# Connectors___Switch_Buttons.net
KiCad netlist of a schematic drawn in Altium Designer
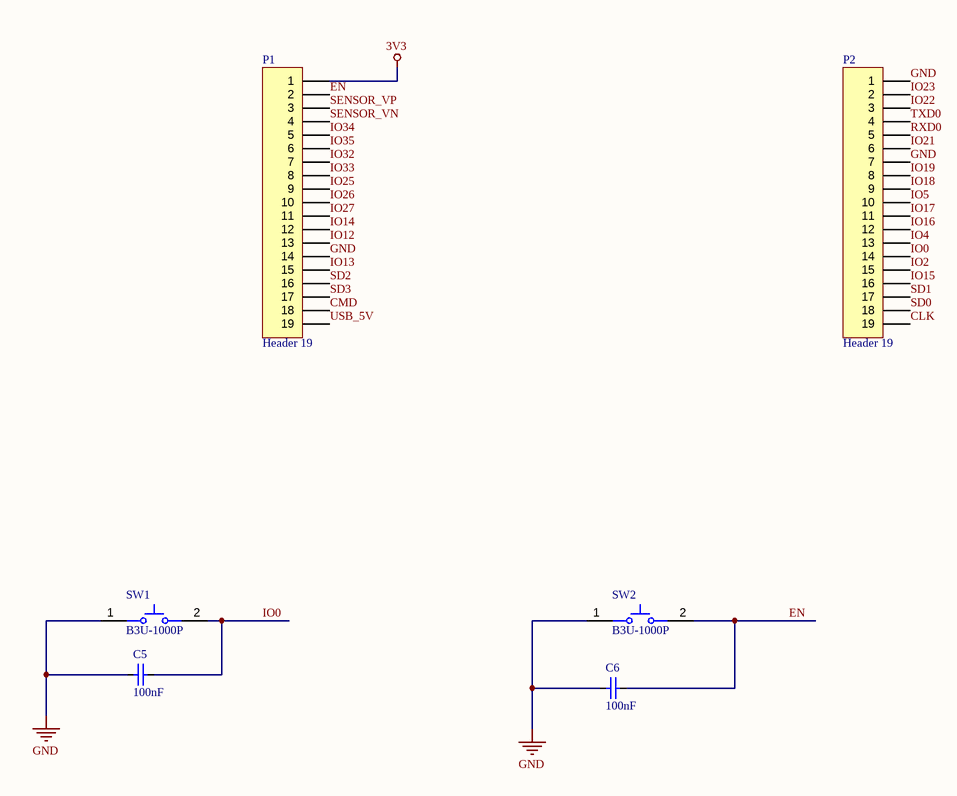
[diagram p0: Connectors_&_Switch_Buttons.SchDoc]

(export (version "E")
  (design (tool "Eeschema 10.0.6"))
  (components
    (comp (ref "C5")
      (value "100nF")
      (footprint "0603C_L")
      (fields
        (field (name "MANUFACTURER") "Yageo")
        (field (name "MANUFACTURER PART NUMBER") "CC0603ZRY5V9BB104")
        (field (name "Comment") "Cap100nF_50V_0603")
        (field (name "SOURCE") "WCT.SCHLIB")
      )
      (libsource (lib "Kylian Siemou Diemou Tchoya") (part "Cap100nF_50V_0603"))
    )
    (comp (ref "C6")
      (value "100nF")
      (footprint "0603C_L")
      (fields
        (field (name "MANUFACTURER") "Yageo")
        (field (name "MANUFACTURER PART NUMBER") "CC0603ZRY5V9BB104")
        (field (name "Comment") "Cap100nF_50V_0603")
        (field (name "SOURCE") "WCT.SCHLIB")
      )
      (libsource (lib "Kylian Siemou Diemou Tchoya") (part "Cap100nF_50V_0603"))
    )
    (comp (ref "P1")
      (value "Header 19")
      (footprint "HDR1X19")
      (description "Header, 19-Pin")
      (fields (field (name "PUBLISHER") "Altium Limited"))
      (libsource (lib "Miscellaneous Connectors") (part "Header 19"))
    )
    (comp (ref "P2")
      (value "Header 19")
      (footprint "HDR1X19")
      (description "Header, 19-Pin")
      (fields (field (name "PUBLISHER") "Altium Limited"))
      (libsource (lib "Miscellaneous Connectors") (part "Header 19"))
    )
    (comp (ref "SW1")
      (value "B3U-1000P")
      (footprint "OMRON-B3U-1000_V")
      (description "Tactile Switch, SPST-NO, 0.05 A, 12 V, -25 to 70 degC, 2-Pin SMD, RoHS, Tape and Reel")
      (fields (field (name "MANUFACTURER") "Omron Electronic Components"))
      (libsource (lib "Kylian Siemou Diemou Tchoya") (part "SW-SPST-NO-2"))
    )
    (comp (ref "SW2")
      (value "B3U-1000P")
      (footprint "OMRON-B3U-1000_V")
      (description "Tactile Switch, SPST-NO, 0.05 A, 12 V, -25 to 70 degC, 2-Pin SMD, RoHS, Tape and Reel")
      (fields (field (name "MANUFACTURER") "Omron Electronic Components"))
      (libsource (lib "Kylian Siemou Diemou Tchoya") (part "SW-SPST-NO-2"))
    )
  )
  (nets
    (net (code "1") (name "/CLK") (class "Default")
      (node (ref "P2") (pin "19") (pinfunction "19_19") (pintype "passive"))
    )
    (net (code "2") (name "/CMD") (class "Default")
      (node (ref "P1") (pin "18") (pinfunction "18_18") (pintype "passive"))
    )
    (net (code "3") (name "/EN") (class "Default")
      (node (ref "C6") (pin "2") (pinfunction "2_2") (pintype "passive"))
      (node (ref "P1") (pin "2") (pinfunction "2_2") (pintype "passive"))
      (node (ref "SW2") (pin "2") (pinfunction "2_2") (pintype "passive"))
    )
    (net (code "4") (name "/IO0") (class "Default")
      (node (ref "C5") (pin "2") (pinfunction "2_2") (pintype "passive"))
      (node (ref "P2") (pin "14") (pinfunction "14_14") (pintype "passive"))
      (node (ref "SW1") (pin "2") (pinfunction "2_2") (pintype "passive"))
    )
    (net (code "5") (name "/IO2") (class "Default")
      (node (ref "P2") (pin "15") (pinfunction "15_15") (pintype "passive"))
    )
    (net (code "6") (name "/IO4") (class "Default")
      (node (ref "P2") (pin "13") (pinfunction "13_13") (pintype "passive"))
    )
    (net (code "7") (name "/IO5") (class "Default")
      (node (ref "P2") (pin "10") (pinfunction "10_10") (pintype "passive"))
    )
    (net (code "8") (name "/IO12") (class "Default")
      (node (ref "P1") (pin "13") (pinfunction "13_13") (pintype "passive"))
    )
    (net (code "9") (name "/IO13") (class "Default")
      (node (ref "P1") (pin "15") (pinfunction "15_15") (pintype "passive"))
    )
    (net (code "10") (name "/IO14") (class "Default")
      (node (ref "P1") (pin "12") (pinfunction "12_12") (pintype "passive"))
    )
    (net (code "11") (name "/IO15") (class "Default")
      (node (ref "P2") (pin "16") (pinfunction "16_16") (pintype "passive"))
    )
    (net (code "12") (name "/IO16") (class "Default")
      (node (ref "P2") (pin "12") (pinfunction "12_12") (pintype "passive"))
    )
    (net (code "13") (name "/IO17") (class "Default")
      (node (ref "P2") (pin "11") (pinfunction "11_11") (pintype "passive"))
    )
    (net (code "14") (name "/IO18") (class "Default")
      (node (ref "P2") (pin "9") (pinfunction "9_9") (pintype "passive"))
    )
    (net (code "15") (name "/IO19") (class "Default")
      (node (ref "P2") (pin "8") (pinfunction "8_8") (pintype "passive"))
    )
    (net (code "16") (name "/IO21") (class "Default")
      (node (ref "P2") (pin "6") (pinfunction "6_6") (pintype "passive"))
    )
    (net (code "17") (name "/IO22") (class "Default")
      (node (ref "P2") (pin "3") (pinfunction "3_3") (pintype "passive"))
    )
    (net (code "18") (name "/IO23") (class "Default")
      (node (ref "P2") (pin "2") (pinfunction "2_2") (pintype "passive"))
    )
    (net (code "19") (name "/IO25") (class "Default")
      (node (ref "P1") (pin "9") (pinfunction "9_9") (pintype "passive"))
    )
    (net (code "20") (name "/IO26") (class "Default")
      (node (ref "P1") (pin "10") (pinfunction "10_10") (pintype "passive"))
    )
    (net (code "21") (name "/IO27") (class "Default")
      (node (ref "P1") (pin "11") (pinfunction "11_11") (pintype "passive"))
    )
    (net (code "22") (name "/IO32") (class "Default")
      (node (ref "P1") (pin "7") (pinfunction "7_7") (pintype "passive"))
    )
    (net (code "23") (name "/IO33") (class "Default")
      (node (ref "P1") (pin "8") (pinfunction "8_8") (pintype "passive"))
    )
    (net (code "24") (name "/IO34") (class "Default")
      (node (ref "P1") (pin "5") (pinfunction "5_5") (pintype "passive"))
    )
    (net (code "25") (name "/IO35") (class "Default")
      (node (ref "P1") (pin "6") (pinfunction "6_6") (pintype "passive"))
    )
    (net (code "26") (name "/RXD0") (class "Default")
      (node (ref "P2") (pin "5") (pinfunction "5_5") (pintype "passive"))
    )
    (net (code "27") (name "/SD0") (class "Default")
      (node (ref "P2") (pin "18") (pinfunction "18_18") (pintype "passive"))
    )
    (net (code "28") (name "/SD1") (class "Default")
      (node (ref "P2") (pin "17") (pinfunction "17_17") (pintype "passive"))
    )
    (net (code "29") (name "/SD2") (class "Default")
      (node (ref "P1") (pin "16") (pinfunction "16_16") (pintype "passive"))
    )
    (net (code "30") (name "/SD3") (class "Default")
      (node (ref "P1") (pin "17") (pinfunction "17_17") (pintype "passive"))
    )
    (net (code "31") (name "/SENSOR_VN") (class "Default")
      (node (ref "P1") (pin "4") (pinfunction "4_4") (pintype "passive"))
    )
    (net (code "32") (name "/SENSOR_VP") (class "Default")
      (node (ref "P1") (pin "3") (pinfunction "3_3") (pintype "passive"))
    )
    (net (code "33") (name "/TXD0") (class "Default")
      (node (ref "P2") (pin "4") (pinfunction "4_4") (pintype "passive"))
    )
    (net (code "34") (name "/USB_5V") (class "Default")
      (node (ref "P1") (pin "19") (pinfunction "19_19") (pintype "passive"))
    )
    (net (code "35") (name "3V3") (class "Default")
      (node (ref "P1") (pin "1") (pinfunction "1_1") (pintype "passive"))
    )
    (net (code "36") (name "GND") (class "Default")
      (node (ref "C5") (pin "1") (pinfunction "1_1") (pintype "passive"))
      (node (ref "C6") (pin "1") (pinfunction "1_1") (pintype "passive"))
      (node (ref "P1") (pin "14") (pinfunction "14_14") (pintype "passive"))
      (node (ref "P2") (pin "1") (pinfunction "1_1") (pintype "passive"))
      (node (ref "P2") (pin "7") (pinfunction "7_7") (pintype "passive"))
      (node (ref "SW1") (pin "1") (pinfunction "1_1") (pintype "passive"))
      (node (ref "SW2") (pin "1") (pinfunction "1_1") (pintype "passive"))
    )
  )
)
